# 3_LORA_MODULE.net
KiCad netlist of a schematic drawn in Altium Designer
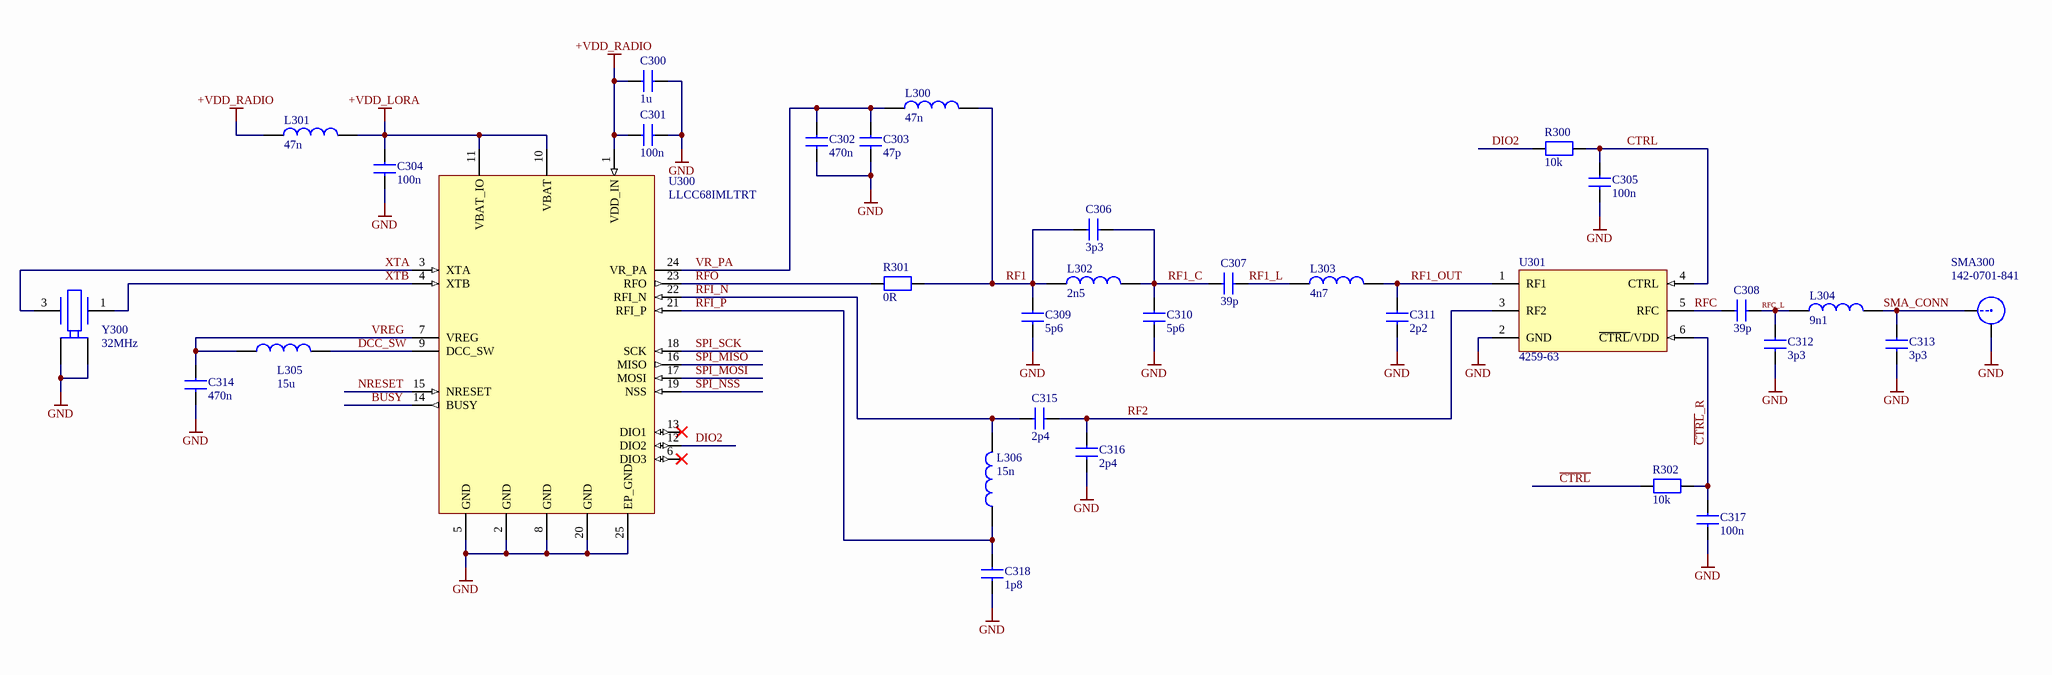
[diagram p0: [3] LORA MODULE.SchDoc]

(export (version "E")
  (design (tool "Eeschema 10.0.6"))
  (components
    (comp (ref "C300")
      (value "1u")
      (footprint "C0402")
      (description "Multilayer Ceramic Capacitor, 1 uF, 10%, X5r, 10 V, 0402 [1005 Metric]")
      (fields
        (field (name "MANUFACTURER") "Walsin Technologies")
        (field (name "MANUFACTURER PART NUMBER") "0402X105K100CT")
      )
      (libsource (lib "ER_SCH_LIB") (part "0402X105K100CT"))
    )
    (comp (ref "C301")
      (value "100n")
      (footprint "C0402")
      (description "Multilayer Ceramic Capacitor, 0.1 uF, 25 V, ± 10%, X7R, 0402 [1005 Metric]")
      (fields
        (field (name "MANUFACTURER") "Kyocera AVX")
        (field (name "MANUFACTURER PART NUMBER") "04023C104KAT2A")
      )
      (libsource (lib "ER_SCH_LIB") (part "04023C104KAT2A"))
    )
    (comp (ref "C302")
      (value "470n")
      (footprint "C0402")
      (description "0402 0.47 uF 10 V ±20% Tolerance X5R SMT Multilayer Ceramic Capacitor")
      (fields
        (field (name "MANUFACTURER") "Murata")
        (field (name "MANUFACTURER PART NUMBER") "GRM155R61A474ME15D")
      )
      (libsource (lib "ER_SCH_LIB") (part "GRM155R61A474ME15D"))
    )
    (comp (ref "C303")
      (value "47p")
      (footprint "C0402")
      (description "0402 47 pF 50 V ±5% Tolerance C0G SMT Multilayer Ceramic Capacitor")
      (fields
        (field (name "MANUFACTURER") "Murata")
        (field (name "MANUFACTURER PART NUMBER") "GRM1555C1H470JA01D")
      )
      (libsource (lib "ER_SCH_LIB") (part "GRM1555C1H470JA01D"))
    )
    (comp (ref "C304")
      (value "100n")
      (footprint "C0402")
      (description "Multilayer Ceramic Capacitor, 0.1 uF, 25 V, ± 10%, X7R, 0402 [1005 Metric]")
      (fields
        (field (name "MANUFACTURER") "Kyocera AVX")
        (field (name "MANUFACTURER PART NUMBER") "04023C104KAT2A")
      )
      (libsource (lib "ER_SCH_LIB") (part "04023C104KAT2A"))
    )
    (comp (ref "C305")
      (value "100n")
      (footprint "C0402")
      (description "Multilayer Ceramic Capacitor, 0.1 uF, 25 V, ± 10%, X7R, 0402 [1005 Metric]")
      (fields
        (field (name "MANUFACTURER") "Kyocera AVX")
        (field (name "MANUFACTURER PART NUMBER") "04023C104KAT2A")
      )
      (libsource (lib "ER_SCH_LIB") (part "04023C104KAT2A"))
    )
    (comp (ref "C306")
      (value "3p3")
      (footprint "C0402")
      (description "0402 3.3 pF 50 V ±0.1 pF Tolerance C0G SMT Multilayer Ceramic Capacitor")
      (fields
        (field (name "MANUFACTURER") "Murata")
        (field (name "MANUFACTURER PART NUMBER") "GRM1555C1H3R3BA01D")
      )
      (libsource (lib "ER_SCH_LIB") (part "GRM1555C1H3R3BA01D"))
    )
    (comp (ref "C307")
      (value "39p")
      (footprint "C0402")
      (description "Multilayer Ceramic Capacitor, 39 pF, 50 V, ± 5%, C0G (NP0), 0402 [1005 Metric]")
      (fields
        (field (name "MANUFACTURER") "Murata")
        (field (name "MANUFACTURER PART NUMBER") "GRM1555C1H390JA01D")
      )
      (libsource (lib "ER_SCH_LIB") (part "GRM1555C1H390JA01D"))
    )
    (comp (ref "C308")
      (value "39p")
      (footprint "C0402")
      (description "Multilayer Ceramic Capacitor, 39 pF, 50 V, ± 5%, C0G (NP0), 0402 [1005 Metric]")
      (fields
        (field (name "MANUFACTURER") "Murata")
        (field (name "MANUFACTURER PART NUMBER") "GRM1555C1H390JA01D")
      )
      (libsource (lib "ER_SCH_LIB") (part "GRM1555C1H390JA01D"))
    )
    (comp (ref "C309")
      (value "5p6")
      (footprint "C0402")
      (description "Multilayer Ceramic Capacitor, 5.6 pF, 50 V, ± 0.25pF, C0G (NP0), 0402 [1005 Metric]")
      (fields
        (field (name "MANUFACTURER") "Murata")
        (field (name "MANUFACTURER PART NUMBER") "GRM1555C1H5R6CA01D")
      )
      (libsource (lib "ER_SCH_LIB") (part "GRM1555C1H5R6CA01D"))
    )
    (comp (ref "C310")
      (value "5p6")
      (footprint "C0402")
      (description "Multilayer Ceramic Capacitor, 5.6 pF, 50 V, ± 0.25pF, C0G (NP0), 0402 [1005 Metric]")
      (fields
        (field (name "MANUFACTURER") "Murata")
        (field (name "MANUFACTURER PART NUMBER") "GRM1555C1H5R6CA01D")
      )
      (libsource (lib "ER_SCH_LIB") (part "GRM1555C1H5R6CA01D"))
    )
    (comp (ref "C311")
      (value "2p2")
      (footprint "C0402")
      (description "CAP CER 2.2PF 50V C0G/NP0 0402")
      (fields
        (field (name "MANUFACTURER") "Murata")
        (field (name "MANUFACTURER PART NUMBER") "GRM1555C1H2R2BA01D")
      )
      (libsource (lib "ER_SCH_LIB") (part "GRM1555C1H2R2BA01D"))
    )
    (comp (ref "C312")
      (value "3p3")
      (footprint "C0402")
      (description "0402 3.3 pF 50 V ±0.1 pF Tolerance C0G SMT Multilayer Ceramic Capacitor")
      (fields
        (field (name "MANUFACTURER") "Murata")
        (field (name "MANUFACTURER PART NUMBER") "GRM1555C1H3R3BA01D")
      )
      (libsource (lib "ER_SCH_LIB") (part "GRM1555C1H3R3BA01D"))
    )
    (comp (ref "C313")
      (value "3p3")
      (footprint "C0402")
      (description "0402 3.3 pF 50 V ±0.1 pF Tolerance C0G SMT Multilayer Ceramic Capacitor")
      (fields
        (field (name "MANUFACTURER") "Murata")
        (field (name "MANUFACTURER PART NUMBER") "GRM1555C1H3R3BA01D")
      )
      (libsource (lib "ER_SCH_LIB") (part "GRM1555C1H3R3BA01D"))
    )
    (comp (ref "C314")
      (value "470n")
      (footprint "C0402")
      (description "0402 0.47 uF 10 V ±20% Tolerance X5R SMT Multilayer Ceramic Capacitor")
      (fields
        (field (name "MANUFACTURER") "Murata")
        (field (name "MANUFACTURER PART NUMBER") "GRM155R61A474ME15D")
      )
      (libsource (lib "ER_SCH_LIB") (part "GRM155R61A474ME15D"))
    )
    (comp (ref "C315")
      (value "2p4")
      (footprint "C0402")
      (description "0402 2.4 pF 50 V ±0.1 pF Tolerance C0G SMT Multilayer Ceramic Capacitor")
      (fields
        (field (name "MANUFACTURER") "Murata")
        (field (name "MANUFACTURER PART NUMBER") "GRM1555C1H2R4BA01D")
      )
      (libsource (lib "ER_SCH_LIB") (part "GRM1555C1H2R4BA01D"))
    )
    (comp (ref "C316")
      (value "2p4")
      (footprint "C0402")
      (description "0402 2.4 pF 50 V ±0.1 pF Tolerance C0G SMT Multilayer Ceramic Capacitor")
      (fields
        (field (name "MANUFACTURER") "Murata")
        (field (name "MANUFACTURER PART NUMBER") "GRM1555C1H2R4BA01D")
      )
      (libsource (lib "ER_SCH_LIB") (part "GRM1555C1H2R4BA01D"))
    )
    (comp (ref "C317")
      (value "100n")
      (footprint "C0402")
      (description "Multilayer Ceramic Capacitor, 0.1 uF, 25 V, ± 10%, X7R, 0402 [1005 Metric]")
      (fields
        (field (name "MANUFACTURER") "Kyocera AVX")
        (field (name "MANUFACTURER PART NUMBER") "04023C104KAT2A")
      )
      (libsource (lib "ER_SCH_LIB") (part "04023C104KAT2A"))
    )
    (comp (ref "C318")
      (value "1p8")
      (footprint "C0402")
      (description "Multilayer Ceramic Capacitor, 1.8 pF, 50 V, ± 0.1pF, C0G (NP0), 0402 [1005 Metric]")
      (fields
        (field (name "MANUFACTURER") "Murata")
        (field (name "MANUFACTURER PART NUMBER") "GRM1555C1H1R8BA01D")
      )
      (libsource (lib "ER_SCH_LIB") (part "GRM1555C1H1R8BA01D"))
    )
    (comp (ref "L300")
      (value "47n")
      (footprint "L0402")
      (description "Inductor RF Chip Wirewound 47nH 5% 100MHz 25Q-Factor 210mA 1.08Ohm DCR 0402 Paper T/R")
      (fields
        (field (name "MANUFACTURER") "Murata")
        (field (name "MANUFACTURER PART NUMBER") "LQW15AN47NJ00D")
      )
      (libsource (lib "ER_SCH_LIB") (part "LQW15AN47NJ00D"))
    )
    (comp (ref "L301")
      (value "47n")
      (footprint "L0402")
      (description "Inductor RF Chip Wirewound 47nH 5% 100MHz 25Q-Factor 210mA 1.08Ohm DCR 0402 Paper T/R")
      (fields
        (field (name "MANUFACTURER") "Murata")
        (field (name "MANUFACTURER PART NUMBER") "LQW15AN47NJ00D")
      )
      (libsource (lib "ER_SCH_LIB") (part "LQW15AN47NJ00D"))
    )
    (comp (ref "L302")
      (value "2n5")
      (footprint "l0402")
      (description "Inductor RF Chip Wirewound 2.5nH 0.2nH 100MHz 20Q-Factor 850mA 50mOhm DCR 0402 Paper T/R")
      (fields
        (field (name "MANUFACTURER") "Murata")
        (field (name "MANUFACTURER PART NUMBER") "LQW15AN2N5C00D")
      )
      (libsource (lib "ER_SCH_LIB") (part "LQW15AN2N5C00D"))
    )
    (comp (ref "L303")
      (value "4n7")
      (footprint "L0402")
      (description "Inductor RF Chip Wirewound 4.7nH 0.2nH 100MHz 25Q-Factor 750mA 70mOhm DCR 0402 Paper T/R")
      (fields
        (field (name "MANUFACTURER") "Murata")
        (field (name "MANUFACTURER PART NUMBER") "LQW15AN4N7C00D")
      )
      (libsource (lib "ER_SCH_LIB") (part "LQW15AN4N7C00D"))
    )
    (comp (ref "L304")
      (value "9n1")
      (footprint "L0402")
      (description "Inductor RF Chip Wirewound 9.1nH 3% 100MHz 25Q-Factor 540mA 140mOhm DCR 0402 Paper T/R")
      (fields
        (field (name "MANUFACTURER") "Murata")
        (field (name "MANUFACTURER PART NUMBER") "LQW15AN9N1H00D")
      )
      (libsource (lib "ER_SCH_LIB") (part "LQW15AN9N1H00D"))
    )
    (comp (ref "L305")
      (value "15u")
      (footprint "L0805")
      (description "Inductor Power Shielded Multi-Layer 15uH 20% 2MHz Ferrite 0.25A 1.235Ohm DCR 0805 T/R")
      (fields
        (field (name "MANUFACTURER") "TDK")
        (field (name "MANUFACTURER PART NUMBER") "MLZ2012M150WT000")
      )
      (libsource (lib "ER_SCH_LIB") (part "MLZ2012M150WT000"))
    )
    (comp (ref "L306")
      (value "15n")
      (footprint "L0402")
      (description "Inductor RF Chip Wirewound 15nH 3% 100MHz 30Q-Factor 460mA 160mOhm DCR 0402 Paper T/R")
      (fields
        (field (name "MANUFACTURER") "Murata")
        (field (name "MANUFACTURER PART NUMBER") "LQW15AN15NH00D")
      )
      (libsource (lib "ER_SCH_LIB") (part "LQW15AN15NH00D"))
    )
    (comp (ref "R300")
      (value "10k")
      (footprint "R0402")
      (description "Res Thick Film 0402 10K Ohm 1% 0.063W(1/16W) ±100ppm/°C Pad SMD T/R")
      (fields
        (field (name "MANUFACTURER") "Royal Electronic Factory")
        (field (name "MANUFACTURER PART NUMBER") "0402WGF1002TCE")
      )
      (libsource (lib "ER_SCH_LIB") (part "0402WGF1002TCE"))
    )
    (comp (ref "R301")
      (value "0R")
      (footprint "R0402")
      (description "CRCW Series 0402 0.063 W 0 Ohm Jumper Surface Mount Thick Film Chip Resistor")
      (fields
        (field (name "MANUFACTURER") "Vishay")
        (field (name "MANUFACTURER PART NUMBER") "CRCW04020000Z0ED")
      )
      (libsource (lib "ER_SCH_LIB") (part "CRCW04020000Z0ED"))
    )
    (comp (ref "R302")
      (value "10k")
      (footprint "R0402")
      (description "Res Thick Film 0402 10K Ohm 1% 0.063W(1/16W) ±100ppm/°C Pad SMD T/R")
      (fields
        (field (name "MANUFACTURER") "Royal Electronic Factory")
        (field (name "MANUFACTURER PART NUMBER") "0402WGF1002TCE")
      )
      (libsource (lib "ER_SCH_LIB") (part "0402WGF1002TCE"))
    )
    (comp (ref "SMA300")
      (value "142-0701-841")
      (footprint "SMA_STRAIGHT_CONN")
      (description "Conn SMA RCP 0Hz to 18GHz 50Ohm Solder ST Edge Mount Gold")
      (fields (field (name "MANUFACTURER") "Bel Cinch"))
      (libsource (lib "ER_SCH_LIB") (part "142-0701-841"))
    )
    (comp (ref "U300")
      (value "LLCC68IMLTRT")
      (footprint "QFN24")
      (description "RF Transceiver LoRa Smart Home low pwr 150-960MHz ISM")
      (libsource (lib "ER_SCH_LIB") (part "LLCC68IMLTRT"))
    )
    (comp (ref "U301")
      (value "4259-63")
      (footprint "SC70")
      (fields (field (name "MANUFACTURER") "Peregrine Semiconductor"))
      (libsource (lib "ER_SCH_LIB") (part "4259-63"))
    )
    (comp (ref "Y300")
      (value "32MHz")
      (footprint "OSCILATOR_5X3_2")
      (description "Rezonator: kwarcowy; 32MHz; ±20ppm; 18pF; SMD; 5x3,2x1mm")
      (fields (field (name "MANUFACTURER PART NUMBER") "LFXTAL059535BULK"))
      (libsource (lib "ER_SCH_LIB") (part "LFXTAL059535BULK"))
    )
  )
  (nets
    (net (code "1") (name "+VDD_LORA") (class "Default")
      (node (ref "C304") (pin "1") (pinfunction "1_1") (pintype "passive"))
      (node (ref "L301") (pin "2") (pinfunction "2_2") (pintype "passive"))
      (node (ref "U300") (pin "10") (pinfunction "VBAT_10") (pintype "power_in"))
      (node (ref "U300") (pin "11") (pinfunction "VBAT_IO_11") (pintype "power_in"))
    )
    (net (code "2") (name "+VDD_RADIO") (class "Default")
      (node (ref "C300") (pin "2") (pinfunction "2_2") (pintype "passive"))
      (node (ref "C301") (pin "2") (pinfunction "2_2") (pintype "passive"))
      (node (ref "L301") (pin "1") (pinfunction "1_1") (pintype "passive"))
      (node (ref "U300") (pin "1") (pinfunction "VDD_IN_1") (pintype "input"))
    )
    (net (code "3") (name "/BUSY") (class "Default")
      (node (ref "U300") (pin "14") (pinfunction "BUSY_14") (pintype "output"))
    )
    (net (code "4") (name "/CTRL") (class "Default")
      (node (ref "C305") (pin "1") (pinfunction "1_1") (pintype "passive"))
      (node (ref "R300") (pin "2") (pinfunction "2_2") (pintype "passive"))
      (node (ref "U301") (pin "4") (pinfunction "CTRL_4") (pintype "input"))
    )
    (net (code "5") (name "/DCC_SW") (class "Default")
      (node (ref "L305") (pin "2") (pinfunction "2_2") (pintype "passive"))
      (node (ref "U300") (pin "9") (pinfunction "DCC_SW_9") (pintype "power_in"))
    )
    (net (code "6") (name "/DIO2") (class "Default")
      (node (ref "R300") (pin "1") (pinfunction "1_1") (pintype "passive"))
      (node (ref "U300") (pin "12") (pinfunction "DIO2_12") (pintype "bidirectional"))
    )
    (net (code "7") (name "/NRESET") (class "Default")
      (node (ref "U300") (pin "15") (pinfunction "NRESET_15") (pintype "input"))
    )
    (net (code "8") (name "/RF1") (class "Default")
      (node (ref "C306") (pin "2") (pinfunction "2_2") (pintype "passive"))
      (node (ref "C309") (pin "2") (pinfunction "2_2") (pintype "passive"))
      (node (ref "L300") (pin "2") (pinfunction "2_2") (pintype "passive"))
      (node (ref "L302") (pin "1") (pinfunction "1_1") (pintype "passive"))
      (node (ref "R301") (pin "2") (pinfunction "2_2") (pintype "passive"))
    )
    (net (code "9") (name "/RF1_C") (class "Default")
      (node (ref "C306") (pin "1") (pinfunction "1_1") (pintype "passive"))
      (node (ref "C307") (pin "2") (pinfunction "2_2") (pintype "passive"))
      (node (ref "C310") (pin "2") (pinfunction "2_2") (pintype "passive"))
      (node (ref "L302") (pin "2") (pinfunction "2_2") (pintype "passive"))
    )
    (net (code "10") (name "/RF1_L") (class "Default")
      (node (ref "C307") (pin "1") (pinfunction "1_1") (pintype "passive"))
      (node (ref "L303") (pin "1") (pinfunction "1_1") (pintype "passive"))
    )
    (net (code "11") (name "/RF1_OUT") (class "Default")
      (node (ref "C311") (pin "2") (pinfunction "2_2") (pintype "passive"))
      (node (ref "L303") (pin "2") (pinfunction "2_2") (pintype "passive"))
      (node (ref "U301") (pin "1") (pinfunction "RF1_1") (pintype "passive"))
    )
    (net (code "12") (name "/RF2") (class "Default")
      (node (ref "C315") (pin "1") (pinfunction "1_1") (pintype "passive"))
      (node (ref "C316") (pin "1") (pinfunction "1_1") (pintype "passive"))
      (node (ref "U301") (pin "3") (pinfunction "RF2_3") (pintype "passive"))
    )
    (net (code "13") (name "/RFC") (class "Default")
      (node (ref "C308") (pin "2") (pinfunction "2_2") (pintype "passive"))
      (node (ref "U301") (pin "5") (pinfunction "RFC_5") (pintype "passive"))
    )
    (net (code "14") (name "/RFC_L") (class "Default")
      (node (ref "C308") (pin "1") (pinfunction "1_1") (pintype "passive"))
      (node (ref "C312") (pin "1") (pinfunction "1_1") (pintype "passive"))
      (node (ref "L304") (pin "1") (pinfunction "1_1") (pintype "passive"))
    )
    (net (code "15") (name "/RFI_N") (class "Default")
      (node (ref "C315") (pin "2") (pinfunction "2_2") (pintype "passive"))
      (node (ref "L306") (pin "2") (pinfunction "2_2") (pintype "passive"))
      (node (ref "U300") (pin "22") (pinfunction "RFI_N_22") (pintype "input"))
    )
    (net (code "16") (name "/RFI_P") (class "Default")
      (node (ref "C318") (pin "2") (pinfunction "2_2") (pintype "passive"))
      (node (ref "L306") (pin "1") (pinfunction "1_1") (pintype "passive"))
      (node (ref "U300") (pin "21") (pinfunction "RFI_P_21") (pintype "input"))
    )
    (net (code "17") (name "/RFO") (class "Default")
      (node (ref "R301") (pin "1") (pinfunction "1_1") (pintype "passive"))
      (node (ref "U300") (pin "23") (pinfunction "RFO_23") (pintype "output"))
    )
    (net (code "18") (name "/SMA_CONN") (class "Default")
      (node (ref "C313") (pin "1") (pinfunction "1_1") (pintype "passive"))
      (node (ref "L304") (pin "2") (pinfunction "2_2") (pintype "passive"))
      (node (ref "SMA300") (pin "1") (pinfunction "1_1") (pintype "power_in"))
    )
    (net (code "19") (name "/SPI_MISO") (class "Default")
      (node (ref "U300") (pin "16") (pinfunction "MISO_16") (pintype "output"))
    )
    (net (code "20") (name "/SPI_MOSI") (class "Default")
      (node (ref "U300") (pin "17") (pinfunction "MOSI_17") (pintype "input"))
    )
    (net (code "21") (name "/SPI_NSS") (class "Default")
      (node (ref "U300") (pin "19") (pinfunction "NSS_19") (pintype "input"))
    )
    (net (code "22") (name "/SPI_SCK") (class "Default")
      (node (ref "U300") (pin "18") (pinfunction "SCK_18") (pintype "input"))
    )
    (net (code "23") (name "/VREG") (class "Default")
      (node (ref "C314") (pin "2") (pinfunction "2_2") (pintype "passive"))
      (node (ref "L305") (pin "1") (pinfunction "1_1") (pintype "passive"))
      (node (ref "U300") (pin "7") (pinfunction "VREG_7") (pintype "power_in"))
    )
    (net (code "24") (name "/VR_PA") (class "Default")
      (node (ref "C302") (pin "2") (pinfunction "2_2") (pintype "passive"))
      (node (ref "C303") (pin "2") (pinfunction "2_2") (pintype "passive"))
      (node (ref "L300") (pin "1") (pinfunction "1_1") (pintype "passive"))
      (node (ref "U300") (pin "24") (pinfunction "VR_PA_24") (pintype "power_in"))
    )
    (net (code "25") (name "/XTA") (class "Default")
      (node (ref "U300") (pin "3") (pinfunction "XTA_3") (pintype "input"))
      (node (ref "Y300") (pin "3") (pinfunction "3_3") (pintype "power_in"))
    )
    (net (code "26") (name "/XTB") (class "Default")
      (node (ref "U300") (pin "4") (pinfunction "XTB_4") (pintype "input"))
      (node (ref "Y300") (pin "1") (pinfunction "1_1") (pintype "power_in"))
    )
    (net (code "27") (name "/~{CTRL}") (class "Default")
      (node (ref "R302") (pin "1") (pinfunction "1_1") (pintype "passive"))
    )
    (net (code "28") (name "/~{CTRL}_R") (class "Default")
      (node (ref "C317") (pin "1") (pinfunction "1_1") (pintype "passive"))
      (node (ref "R302") (pin "2") (pinfunction "2_2") (pintype "passive"))
      (node (ref "U301") (pin "6") (pinfunction "~{CTRL}/VDD_6") (pintype "input"))
    )
    (net (code "29") (name "GND") (class "Default")
      (node (ref "C300") (pin "1") (pinfunction "1_1") (pintype "passive"))
      (node (ref "C301") (pin "1") (pinfunction "1_1") (pintype "passive"))
      (node (ref "C302") (pin "1") (pinfunction "1_1") (pintype "passive"))
      (node (ref "C303") (pin "1") (pinfunction "1_1") (pintype "passive"))
      (node (ref "C304") (pin "2") (pinfunction "2_2") (pintype "passive"))
      (node (ref "C305") (pin "2") (pinfunction "2_2") (pintype "passive"))
      (node (ref "C309") (pin "1") (pinfunction "1_1") (pintype "passive"))
      (node (ref "C310") (pin "1") (pinfunction "1_1") (pintype "passive"))
      (node (ref "C311") (pin "1") (pinfunction "1_1") (pintype "passive"))
      (node (ref "C312") (pin "2") (pinfunction "2_2") (pintype "passive"))
      (node (ref "C313") (pin "2") (pinfunction "2_2") (pintype "passive"))
      (node (ref "C314") (pin "1") (pinfunction "1_1") (pintype "passive"))
      (node (ref "C316") (pin "2") (pinfunction "2_2") (pintype "passive"))
      (node (ref "C317") (pin "2") (pinfunction "2_2") (pintype "passive"))
      (node (ref "C318") (pin "1") (pinfunction "1_1") (pintype "passive"))
      (node (ref "SMA300") (pin "2") (pinfunction "2_2") (pintype "power_in"))
      (node (ref "U300") (pin "2") (pinfunction "GND_2") (pintype "power_in"))
      (node (ref "U300") (pin "20") (pinfunction "GND_20") (pintype "power_in"))
      (node (ref "U300") (pin "25") (pinfunction "EP_GND_25") (pintype "power_in"))
      (node (ref "U300") (pin "5") (pinfunction "GND_5") (pintype "power_in"))
      (node (ref "U300") (pin "8") (pinfunction "GND_8") (pintype "power_in"))
      (node (ref "U301") (pin "2") (pinfunction "GND_2") (pintype "power_in"))
      (node (ref "Y300") (pin "2") (pinfunction "2_2") (pintype "power_in"))
      (node (ref "Y300") (pin "4") (pinfunction "4_4") (pintype "power_in"))
    )
    (net (code "30") (name "unconnected-(U300-DIO1-Pad13)") (class "Default")
      (node (ref "U300") (pin "13") (pinfunction "DIO1_13") (pintype "bidirectional+no_connect"))
    )
    (net (code "31") (name "unconnected-(U300-DIO3-Pad6)") (class "Default")
      (node (ref "U300") (pin "6") (pinfunction "DIO3_6") (pintype "bidirectional+no_connect"))
    )
  )
)
